# EFNMR_POWER_V1.net
KiCad netlist of a schematic drawn in Altium Designer
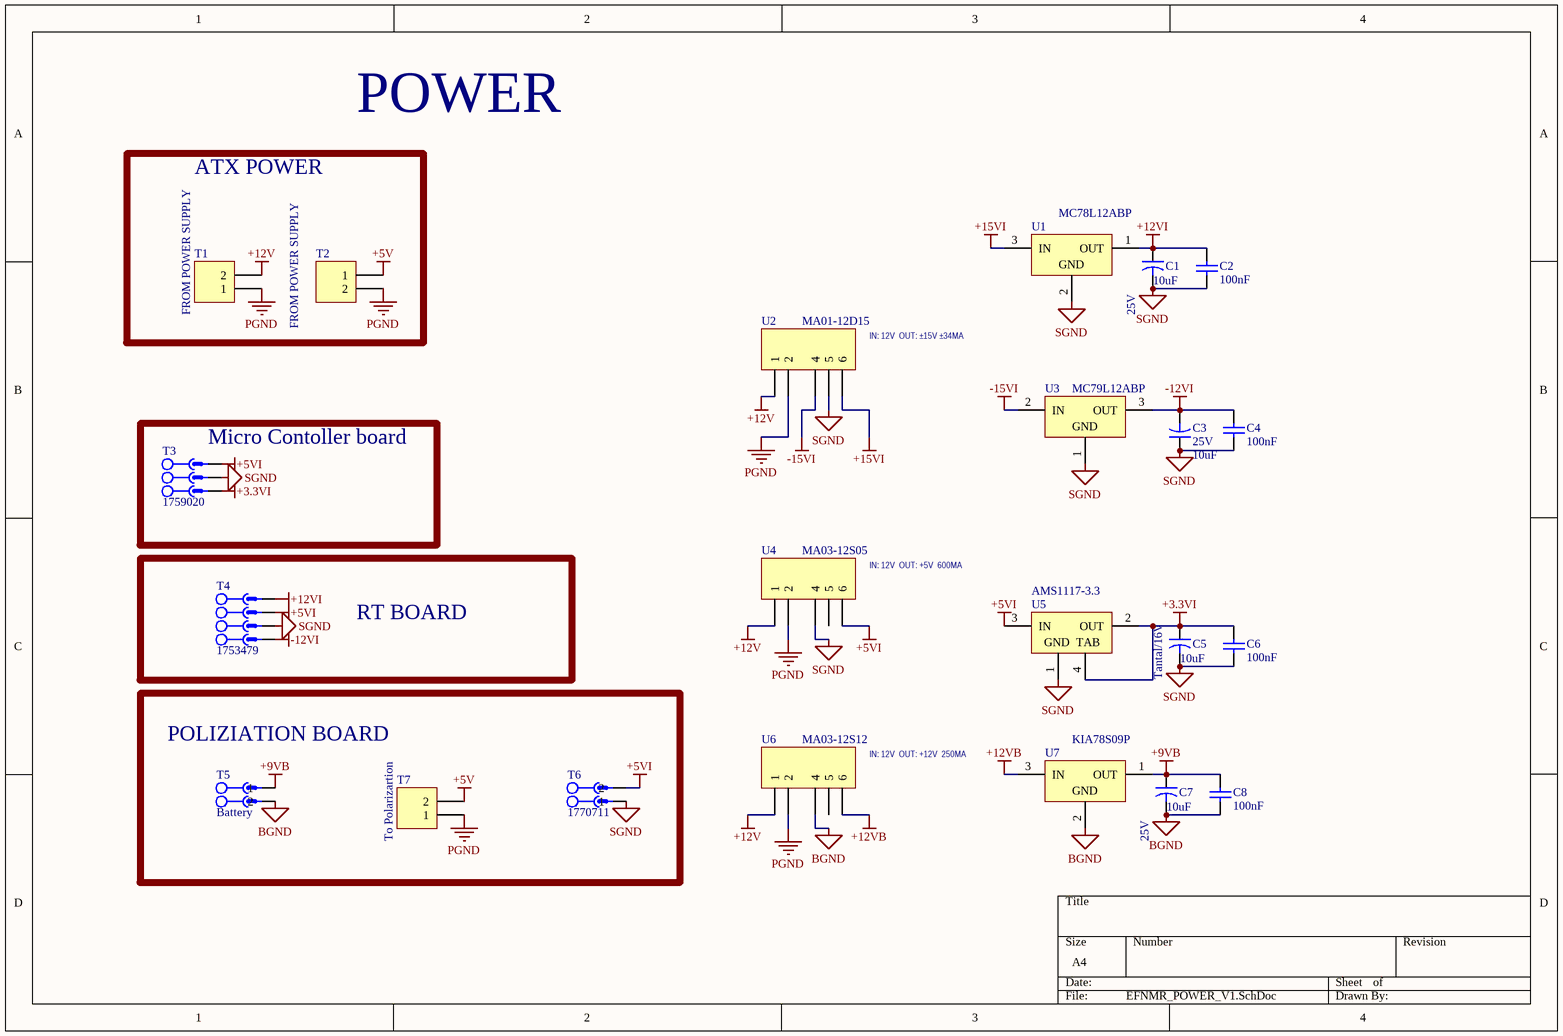
[diagram p0: EFNMR_POWER_V1.SchDoc]

(export (version "E")
  (design (tool "Eeschema 10.0.6"))
  (components
    (comp (ref "C1")
      (value "25V")
      (footprint "CAP_TANTAL_TYPE_C")
      (description "Capacitor")
      (fields (field (name "ALTIUM_VALUE") "10uF") (field (name "PUBLISHER") "Altium Limited"))
      (libsource (lib "Miscellaneous Devices") (part "Cap2"))
    )
    (comp (ref "C2")
      (value "100nF")
      (footprint "Cap0805")
      (description "Capacitor")
      (fields (field (name "Comment") "Cap") (field (name "PUBLISHER") "Altium Limited"))
      (libsource (lib "Miscellaneous Devices") (part "Cap"))
    )
    (comp (ref "C3")
      (value "25V")
      (footprint "CAP_TANTAL_TYPE_C")
      (description "Capacitor")
      (fields (field (name "ALTIUM_VALUE") "10uF") (field (name "PUBLISHER") "Altium Limited"))
      (libsource (lib "Miscellaneous Devices") (part "Cap2"))
    )
    (comp (ref "C4")
      (value "100nF")
      (footprint "Cap0805")
      (description "Capacitor")
      (fields (field (name "Comment") "Cap") (field (name "PUBLISHER") "Altium Limited"))
      (libsource (lib "Miscellaneous Devices") (part "Cap"))
    )
    (comp (ref "C5")
      (value "Tantal/16V")
      (footprint "CAP_TANTAL_TYPE_C")
      (description "Capacitor")
      (fields (field (name "ALTIUM_VALUE") "10uF") (field (name "PUBLISHER") "Altium Limited"))
      (libsource (lib "Miscellaneous Devices") (part "Cap2"))
    )
    (comp (ref "C6")
      (value "100nF")
      (footprint "Cap0805")
      (description "Capacitor")
      (fields (field (name "Comment") "Cap") (field (name "PUBLISHER") "Altium Limited"))
      (libsource (lib "Miscellaneous Devices") (part "Cap"))
    )
    (comp (ref "C7")
      (value "25V")
      (footprint "CAP_TANTAL_TYPE_C")
      (description "Capacitor")
      (fields (field (name "ALTIUM_VALUE") "10uF") (field (name "PUBLISHER") "Altium Limited"))
      (libsource (lib "Miscellaneous Devices") (part "Cap2"))
    )
    (comp (ref "C8")
      (value "100nF")
      (footprint "Cap0805")
      (description "Capacitor")
      (fields (field (name "Comment") "Cap") (field (name "PUBLISHER") "Altium Limited"))
      (libsource (lib "Miscellaneous Devices") (part "Cap"))
    )
    (comp (ref "T1")
      (value "FROM POWER SUPPLY")
      (footprint "KF35C 2PIN")
      (description "Header, 2-Pin")
      (fields (field (name "PUBLISHER") "Altium Limited"))
      (libsource (lib "") (part "Header 2_1"))
    )
    (comp (ref "T2")
      (value "FROM POWER SUPPLY")
      (footprint "KF35C 2PIN")
      (description "Header, 2-Pin")
      (fields (field (name "PUBLISHER") "Altium Limited"))
      (libsource (lib "Miscellaneous Connectors") (part "Header 2"))
    )
    (comp (ref "T3")
      (value "1759020")
      (footprint "MSTB 2,5/3-G-5,08")
      (description "3 Pitch: 5.08 mm Color: green Contact surface: Tin Assembly")
      (fields
        (field (name "MANUFACTURER") "PHOENIX CONTACT")
        (field (name "VOLTAGE") "320 V")
        (field (name "DESIGNER") "ABBAS BASEREH")
      )
      (libsource (lib "Mofidi3D") (part "CON_Phoenix_MSTB_03"))
    )
    (comp (ref "T4")
      (value "1753479")
      (footprint "MSTB 2,5/4-G-5,08")
      (description "4 Pitch: 5 mm Color: green Contact surface: Tin Assembly")
      (fields
        (field (name "MANUFACTURER") "PHOENIX CONTACT")
        (field (name "VOLTAGE") "320 V")
        (field (name "DESIGNER") "ABBAS BASEREH")
      )
      (libsource (lib "Mofidi3D") (part "CON_Phoenix_MSTBV_04"))
    )
    (comp (ref "T5")
      (value "Battery")
      (footprint "MSTB 2,5/2-G-5,08")
      (description "2 Pitch: 5.08 mm Color: green Contact surface: Tin Assembly")
      (fields
        (field (name "MANUFACTURER") "PHOENIX CONTACT")
        (field (name "VOLTAGE") "320 V")
        (field (name "DESIGNER") "ABBAS BASEREH")
      )
      (libsource (lib "") (part "CON_Phoenix_MSTB_02_1"))
    )
    (comp (ref "T6")
      (value "1770711")
      (footprint "MSTB 2,5/2-G-5,08")
      (description "2 Pitch: 5.08 mm Color: green Contact surface: Tin Assembly")
      (fields
        (field (name "MANUFACTURER") "PHOENIX CONTACT")
        (field (name "VOLTAGE") "320 V")
        (field (name "DESIGNER") "ABBAS BASEREH")
      )
      (libsource (lib "Mofidi3D") (part "CON_Phoenix_MSTB_02"))
    )
    (comp (ref "T7")
      (value "To Polarizartion")
      (footprint "KF35C 2PIN")
      (description "Header, 2-Pin")
      (fields (field (name "PUBLISHER") "Altium Limited"))
      (libsource (lib "") (part "Header 2_1"))
    )
    (comp (ref "U1")
      (value "MC78L12ABP")
      (footprint "TO-92 STR")
      (description "3-Terminal Low-Current Positive Fixed Voltage Regulator")
      (fields (field (name "PUBLISHER") "Altium Limited"))
      (libsource (lib "Motorola Power Mgt Voltage Regulator") (part "MC78L12ABP"))
    )
    (comp (ref "U2")
      (value "MA01-12D15")
      (footprint "MA01-MINMAX")
      (description "Header, 6-Pin")
      (fields (field (name "PUBLISHER") "Altium Limited"))
      (libsource (lib "Miscellaneous Connectors") (part "Header 6"))
    )
    (comp (ref "U3")
      (value "MC79L12ABP")
      (footprint "TO-92 STR")
      (description "Three-Terminal Low-Current Negative Fixed Voltage Regulator")
      (fields (field (name "PUBLISHER") "Altium Limited"))
      (libsource (lib "Motorola Power Mgt Voltage Regulator") (part "MC79L12ABP"))
    )
    (comp (ref "U4")
      (value "MA03-12S05")
      (footprint "MA03-S-MINIMAX")
      (description "Header, 6-Pin")
      (fields (field (name "PUBLISHER") "Altium Limited"))
      (libsource (lib "Miscellaneous Connectors") (part "Header 6"))
    )
    (comp (ref "U5")
      (value "AMS1117-3.3")
      (footprint "SOT223_4")
      (description "3.3V, 1A General Purpose LDO")
      (libsource (lib "Holtek Semiconductor Power Management") (part "HT1117-33_SOT223"))
    )
    (comp (ref "U6")
      (value "MA03-12S12")
      (footprint "MA03-S-MINIMAX")
      (description "Header, 6-Pin")
      (fields (field (name "PUBLISHER") "Altium Limited"))
      (libsource (lib "Miscellaneous Connectors") (part "Header 6"))
    )
    (comp (ref "U7")
      (value "KIA78S09P")
      (footprint "TO-92 STR")
      (description "3-Terminal Low-Current Positive Fixed Voltage Regulator")
      (fields (field (name "PUBLISHER") "Altium Limited"))
      (libsource (lib "Motorola Power Mgt Voltage Regulator") (part "MC78L12ABP"))
    )
  )
  (nets
    (net (code "1") (name "+3.3VI") (class "Default")
      (node (ref "C5") (pin "1") (pinfunction "1_1") (pintype "passive"))
      (node (ref "C6") (pin "2") (pinfunction "2_2") (pintype "passive"))
      (node (ref "T3") (pin "1") (pinfunction "1_1") (pintype "passive"))
      (node (ref "U5") (pin "2") (pinfunction "OUT_2") (pintype "power_in"))
      (node (ref "U5") (pin "4") (pinfunction "TAB_4") (pintype "power_in"))
    )
    (net (code "2") (name "+5V") (class "Default")
      (node (ref "T2") (pin "1") (pinfunction "1_1") (pintype "passive"))
      (node (ref "T7") (pin "2") (pinfunction "2_2") (pintype "passive"))
    )
    (net (code "3") (name "+5VI") (class "Default")
      (node (ref "T3") (pin "3") (pinfunction "3_3") (pintype "passive"))
      (node (ref "T4") (pin "3") (pinfunction "3_3") (pintype "passive"))
      (node (ref "T6") (pin "2") (pinfunction "2_2") (pintype "passive"))
      (node (ref "U4") (pin "6") (pinfunction "6_6") (pintype "passive"))
      (node (ref "U5") (pin "3") (pinfunction "IN_3") (pintype "power_in"))
    )
    (net (code "4") (name "+9VB") (class "Default")
      (node (ref "C7") (pin "1") (pinfunction "1_1") (pintype "passive"))
      (node (ref "C8") (pin "2") (pinfunction "2_2") (pintype "passive"))
      (node (ref "T5") (pin "1") (pinfunction "1_1") (pintype "passive"))
      (node (ref "U7") (pin "1") (pinfunction "OUT_1") (pintype "power_in"))
    )
    (net (code "5") (name "+12V") (class "Default")
      (node (ref "T1") (pin "2") (pinfunction "2_2") (pintype "passive"))
      (node (ref "U2") (pin "1") (pinfunction "1_1") (pintype "passive"))
      (node (ref "U4") (pin "1") (pinfunction "1_1") (pintype "passive"))
      (node (ref "U6") (pin "1") (pinfunction "1_1") (pintype "passive"))
    )
    (net (code "6") (name "+12VB") (class "Default")
      (node (ref "U6") (pin "6") (pinfunction "6_6") (pintype "passive"))
      (node (ref "U7") (pin "3") (pinfunction "IN_3") (pintype "power_in"))
    )
    (net (code "7") (name "+12VI") (class "Default")
      (node (ref "C1") (pin "1") (pinfunction "1_1") (pintype "passive"))
      (node (ref "C2") (pin "2") (pinfunction "2_2") (pintype "passive"))
      (node (ref "T4") (pin "4") (pinfunction "4_4") (pintype "passive"))
      (node (ref "U1") (pin "1") (pinfunction "OUT_1") (pintype "power_in"))
    )
    (net (code "8") (name "+15VI") (class "Default")
      (node (ref "U1") (pin "3") (pinfunction "IN_3") (pintype "power_in"))
      (node (ref "U2") (pin "6") (pinfunction "6_6") (pintype "passive"))
    )
    (net (code "9") (name "-12VI") (class "Default")
      (node (ref "C3") (pin "2") (pinfunction "2_2") (pintype "passive"))
      (node (ref "C4") (pin "2") (pinfunction "2_2") (pintype "passive"))
      (node (ref "T4") (pin "1") (pinfunction "1_1") (pintype "passive"))
      (node (ref "U3") (pin "3") (pinfunction "OUT_3") (pintype "power_in"))
    )
    (net (code "10") (name "-15VI") (class "Default")
      (node (ref "U2") (pin "4") (pinfunction "4_4") (pintype "passive"))
      (node (ref "U3") (pin "2") (pinfunction "IN_2") (pintype "power_in"))
    )
    (net (code "11") (name "BGND") (class "Default")
      (node (ref "C7") (pin "2") (pinfunction "2_2") (pintype "passive"))
      (node (ref "C8") (pin "1") (pinfunction "1_1") (pintype "passive"))
      (node (ref "T5") (pin "2") (pinfunction "2_2") (pintype "passive"))
      (node (ref "U6") (pin "4") (pinfunction "4_4") (pintype "passive"))
      (node (ref "U7") (pin "2") (pinfunction "GND_2") (pintype "power_in"))
    )
    (net (code "12") (name "PGND") (class "Default")
      (node (ref "T1") (pin "1") (pinfunction "1_1") (pintype "passive"))
      (node (ref "T2") (pin "2") (pinfunction "2_2") (pintype "passive"))
      (node (ref "T7") (pin "1") (pinfunction "1_1") (pintype "passive"))
      (node (ref "U2") (pin "2") (pinfunction "2_2") (pintype "passive"))
      (node (ref "U4") (pin "2") (pinfunction "2_2") (pintype "passive"))
      (node (ref "U6") (pin "2") (pinfunction "2_2") (pintype "passive"))
    )
    (net (code "13") (name "SGND") (class "Default")
      (node (ref "C1") (pin "2") (pinfunction "2_2") (pintype "passive"))
      (node (ref "C2") (pin "1") (pinfunction "1_1") (pintype "passive"))
      (node (ref "C3") (pin "1") (pinfunction "1_1") (pintype "passive"))
      (node (ref "C4") (pin "1") (pinfunction "1_1") (pintype "passive"))
      (node (ref "C5") (pin "2") (pinfunction "2_2") (pintype "passive"))
      (node (ref "C6") (pin "1") (pinfunction "1_1") (pintype "passive"))
      (node (ref "T3") (pin "2") (pinfunction "2_2") (pintype "passive"))
      (node (ref "T4") (pin "2") (pinfunction "2_2") (pintype "passive"))
      (node (ref "T6") (pin "1") (pinfunction "1_1") (pintype "passive"))
      (node (ref "U1") (pin "2") (pinfunction "GND_2") (pintype "power_in"))
      (node (ref "U2") (pin "5") (pinfunction "5_5") (pintype "passive"))
      (node (ref "U3") (pin "1") (pinfunction "GND_1") (pintype "power_in"))
      (node (ref "U4") (pin "4") (pinfunction "4_4") (pintype "passive"))
      (node (ref "U5") (pin "1") (pinfunction "GND_1") (pintype "power_in"))
    )
    (net (code "14") (name "unconnected-(U4-Pad5)") (class "Default")
      (node (ref "U4") (pin "5") (pinfunction "5_5") (pintype "passive"))
    )
    (net (code "15") (name "unconnected-(U6-Pad5)") (class "Default")
      (node (ref "U6") (pin "5") (pinfunction "5_5") (pintype "passive"))
    )
  )
)
